# LEDs.net
KiCad netlist of a schematic drawn in Altium Designer
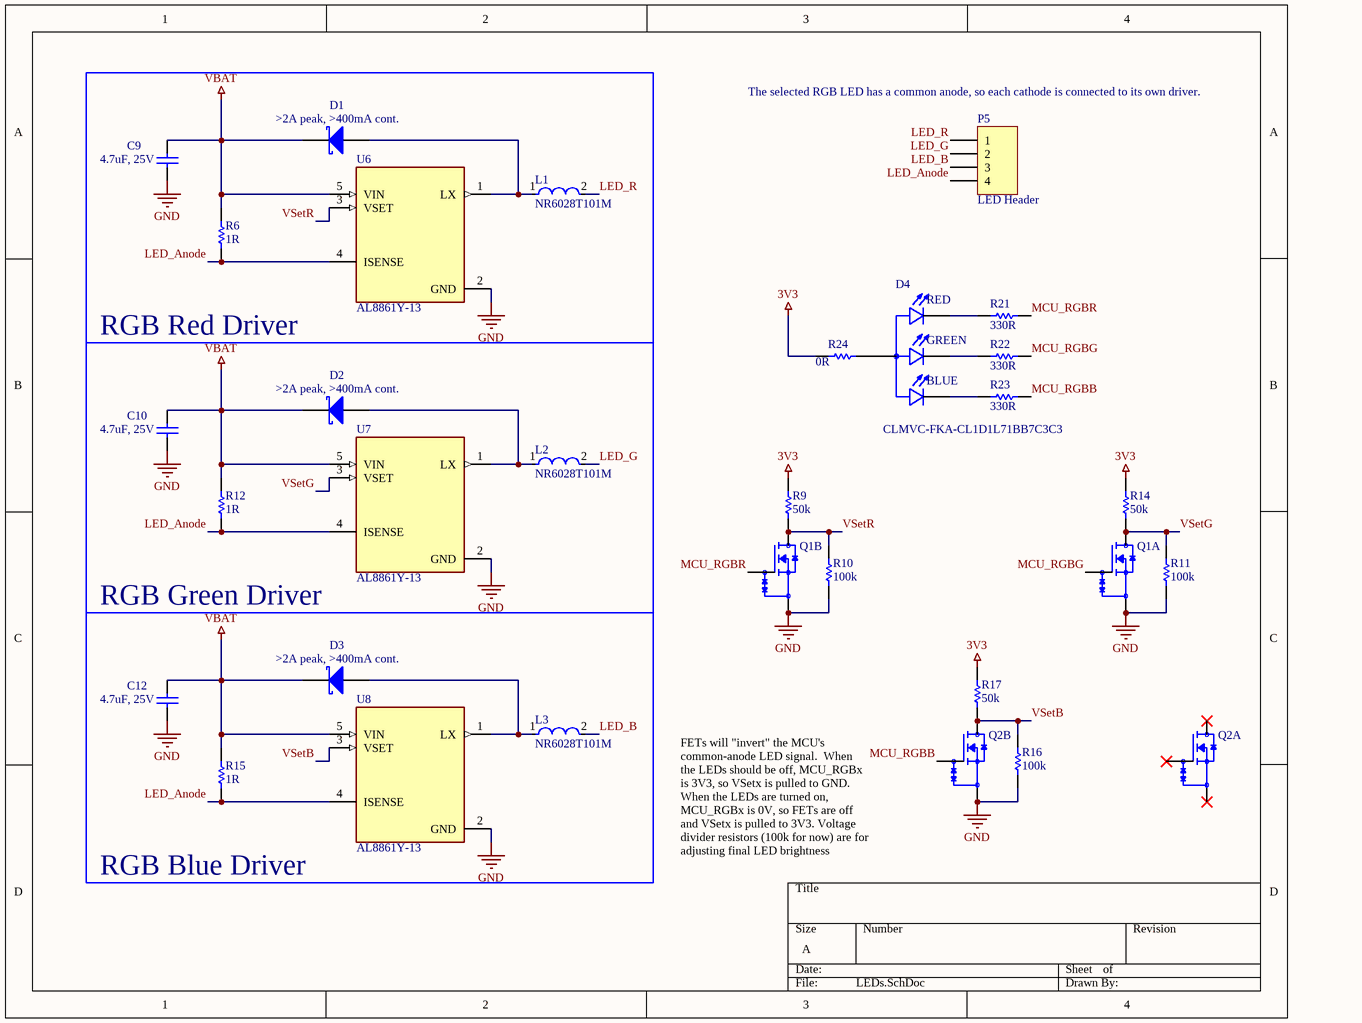
[diagram p0: LEDs.SchDoc]

(export (version "E")
  (design (tool "Eeschema 10.0.6"))
  (components
    (comp (ref "C9")
      (value "4.7uF, 25V")
      (footprint "ANTC1608X90N")
      (description "Capacitor")
      (libsource (lib "Simulation Generic Components") (part "Capacitor"))
    )
    (comp (ref "C10")
      (value "4.7uF, 25V")
      (footprint "ANTC1608X90N")
      (description "Capacitor")
      (libsource (lib "Simulation Generic Components") (part "Capacitor"))
    )
    (comp (ref "C12")
      (value "4.7uF, 25V")
      (footprint "ANTC1608X90N")
      (description "Capacitor")
      (libsource (lib "Simulation Generic Components") (part "Capacitor"))
    )
    (comp (ref "D1")
      (value ">2A peak, >400mA cont.")
      (footprint "DIO_SS26FL")
      (description "Shottky Diode")
      (libsource (lib "Simulation Generic Components") (part "Shottky Diode"))
    )
    (comp (ref "D2")
      (value ">2A peak, >400mA cont.")
      (footprint "DIO_SS26FL")
      (description "Shottky Diode")
      (libsource (lib "Simulation Generic Components") (part "Shottky Diode"))
    )
    (comp (ref "D3")
      (value ">2A peak, >400mA cont.")
      (footprint "DIO_SS26FL")
      (description "Shottky Diode")
      (libsource (lib "Simulation Generic Components") (part "Shottky Diode"))
    )
    (comp (ref "D4")
      (value "CLMVC-FKA-CL1D1L71BB7C3C3")
      (footprint "LED_CLMVC-FKA-CL1D1L71BB7C3C3")
      (fields (field (name "MF") "Cree Inc."))
      (libsource (lib "CLMVC-FKA-CL1D1L71BB7C3C3") (part "CLMVC-FKA-CL1D1L71BB7C3C3"))
    )
    (comp (ref "L1")
      (value "NR6028T101M")
      (footprint "FP-NR6028-MFG")
      (description "SMD Power Inductors 100uH ±20% 0.62A 0.78Ω")
      (fields (field (name "TOLERANCE") "20%"))
      (libsource (lib "Altium Content Vault") (part "725321dda6339637d4d059423bc1c3c"))
    )
    (comp (ref "L2")
      (value "NR6028T101M")
      (footprint "FP-NR6028-MFG")
      (description "SMD Power Inductors 100uH ±20% 0.62A 0.78Ω")
      (fields (field (name "TOLERANCE") "20%"))
      (libsource (lib "Altium Content Vault") (part "725321dda6339637d4d059423bc1c3c"))
    )
    (comp (ref "L3")
      (value "NR6028T101M")
      (footprint "FP-NR6028-MFG")
      (description "SMD Power Inductors 100uH ±20% 0.62A 0.78Ω")
      (fields (field (name "TOLERANCE") "20%"))
      (libsource (lib "Altium Content Vault") (part "725321dda6339637d4d059423bc1c3c"))
    )
    (comp (ref "P5")
      (value "LED Header")
      (footprint "TE_350761-4")
      (description "Header, 4-Pin")
      (fields (field (name "PUBLISHER") "Altium Limited"))
      (libsource (lib "Miscellaneous Connectors") (part "Header 4"))
    )
    (comp (ref "Q1")
      (value "TSM2N7002KDCU6_RFG")
      (footprint "SOT65P210X110-6N")
      (description "60V, 0.22A, Dual N-Channel Power MOSFET")
      (fields (field (name "MF") "Taiwan Semiconductor") (field (name "MP") "TSM2N7002KDCU6 RFG"))
      (libsource (lib "TSM2N7002KDCU6_RFG") (part "TSM2N7002KDCU6_RFG"))
    )
    (comp (ref "Q2")
      (value "TSM2N7002KDCU6_RFG")
      (footprint "SOT65P210X110-6N")
      (description "60V, 0.22A, Dual N-Channel Power MOSFET")
      (fields (field (name "MF") "Taiwan Semiconductor") (field (name "MP") "TSM2N7002KDCU6 RFG"))
      (libsource (lib "TSM2N7002KDCU6_RFG") (part "TSM2N7002KDCU6_RFG"))
    )
    (comp (ref "R6")
      (value "1R")
      (footprint "0603 Resistor")
      (description "Resistor")
      (libsource (lib "Simulation Generic Components") (part "Resistor"))
    )
    (comp (ref "R9")
      (value "50k")
      (footprint "0603 Resistor")
      (description "Resistor")
      (libsource (lib "Simulation Generic Components") (part "Resistor"))
    )
    (comp (ref "R10")
      (value "100k")
      (footprint "0603 Resistor")
      (description "Resistor")
      (libsource (lib "Simulation Generic Components") (part "Resistor"))
    )
    (comp (ref "R11")
      (value "100k")
      (footprint "0603 Resistor")
      (description "Resistor")
      (libsource (lib "Simulation Generic Components") (part "Resistor"))
    )
    (comp (ref "R12")
      (value "1R")
      (footprint "0603 Resistor")
      (description "Resistor")
      (libsource (lib "Simulation Generic Components") (part "Resistor"))
    )
    (comp (ref "R14")
      (value "50k")
      (footprint "0603 Resistor")
      (description "Resistor")
      (libsource (lib "Simulation Generic Components") (part "Resistor"))
    )
    (comp (ref "R15")
      (value "1R")
      (footprint "0603 Resistor")
      (description "Resistor")
      (libsource (lib "Simulation Generic Components") (part "Resistor"))
    )
    (comp (ref "R16")
      (value "100k")
      (footprint "0603 Resistor")
      (description "Resistor")
      (libsource (lib "Simulation Generic Components") (part "Resistor"))
    )
    (comp (ref "R17")
      (value "50k")
      (footprint "0603 Resistor")
      (description "Resistor")
      (libsource (lib "Simulation Generic Components") (part "Resistor"))
    )
    (comp (ref "R21")
      (value "330R")
      (footprint "0603 Resistor")
      (description "Resistor")
      (libsource (lib "Simulation Generic Components") (part "Resistor"))
    )
    (comp (ref "R22")
      (value "330R")
      (footprint "0603 Resistor")
      (description "Resistor")
      (libsource (lib "Simulation Generic Components") (part "Resistor"))
    )
    (comp (ref "R23")
      (value "330R")
      (footprint "0603 Resistor")
      (description "Resistor")
      (libsource (lib "Simulation Generic Components") (part "Resistor"))
    )
    (comp (ref "R24")
      (value "0R")
      (footprint "0603 Resistor")
      (description "Resistor")
      (libsource (lib "Simulation Generic Components") (part "Resistor"))
    )
    (comp (ref "U6")
      (value "AL8861Y-13")
      (footprint "CONV_AL8861Y-13")
      (description "LED Driver IC 1 Output DC DC Regulator Step-Down _Buck_ Analog, PWM Dimming 1.5A SOT-89-5")
      (fields (field (name "MF") "Diodes Inc."))
      (libsource (lib "AL8861Y-13") (part "AL8861Y-13"))
    )
    (comp (ref "U7")
      (value "AL8861Y-13")
      (footprint "CONV_AL8861Y-13")
      (description "LED Driver IC 1 Output DC DC Regulator Step-Down _Buck_ Analog, PWM Dimming 1.5A SOT-89-5")
      (fields (field (name "MF") "Diodes Inc."))
      (libsource (lib "AL8861Y-13") (part "AL8861Y-13"))
    )
    (comp (ref "U8")
      (value "AL8861Y-13")
      (footprint "CONV_AL8861Y-13")
      (description "LED Driver IC 1 Output DC DC Regulator Step-Down _Buck_ Analog, PWM Dimming 1.5A SOT-89-5")
      (fields (field (name "MF") "Diodes Inc."))
      (libsource (lib "AL8861Y-13") (part "AL8861Y-13"))
    )
  )
  (nets
    (net (code "1") (name "/LED_Anode") (class "Default")
      (node (ref "P5") (pin "4") (pinfunction "4_4") (pintype "passive"))
      (node (ref "R12") (pin "2") (pinfunction "2_2") (pintype "passive"))
      (node (ref "R15") (pin "2") (pinfunction "2_2") (pintype "passive"))
      (node (ref "R6") (pin "2") (pinfunction "2_2") (pintype "passive"))
      (node (ref "U6") (pin "4") (pinfunction "ISENSE_4") (pintype "passive"))
      (node (ref "U7") (pin "4") (pinfunction "ISENSE_4") (pintype "passive"))
      (node (ref "U8") (pin "4") (pinfunction "ISENSE_4") (pintype "passive"))
    )
    (net (code "2") (name "/LED_B") (class "Default")
      (node (ref "L3") (pin "2") (pinfunction "2_2") (pintype "passive"))
      (node (ref "P5") (pin "3") (pinfunction "3_3") (pintype "passive"))
    )
    (net (code "3") (name "/LED_G") (class "Default")
      (node (ref "L2") (pin "2") (pinfunction "2_2") (pintype "passive"))
      (node (ref "P5") (pin "2") (pinfunction "2_2") (pintype "passive"))
    )
    (net (code "4") (name "/LED_R") (class "Default")
      (node (ref "L1") (pin "2") (pinfunction "2_2") (pintype "passive"))
      (node (ref "P5") (pin "1") (pinfunction "1_1") (pintype "passive"))
    )
    (net (code "5") (name "/MCU_RGBB") (class "Default")
      (node (ref "Q2") (pin "5") (pinfunction "G2_5") (pintype "passive"))
      (node (ref "R23") (pin "2") (pinfunction "2_2") (pintype "passive"))
    )
    (net (code "6") (name "/MCU_RGBG") (class "Default")
      (node (ref "Q1") (pin "2") (pinfunction "G1_2") (pintype "passive"))
      (node (ref "R22") (pin "2") (pinfunction "2_2") (pintype "passive"))
    )
    (net (code "7") (name "/MCU_RGBR") (class "Default")
      (node (ref "Q1") (pin "5") (pinfunction "G2_5") (pintype "passive"))
      (node (ref "R21") (pin "2") (pinfunction "2_2") (pintype "passive"))
    )
    (net (code "8") (name "/VSetB") (class "Default")
      (node (ref "Q2") (pin "3") (pinfunction "D2_3") (pintype "passive"))
      (node (ref "R16") (pin "2") (pinfunction "2_2") (pintype "passive"))
      (node (ref "R17") (pin "1") (pinfunction "1_1") (pintype "passive"))
      (node (ref "U8") (pin "3") (pinfunction "VSET_3") (pintype "input"))
    )
    (net (code "9") (name "/VSetG") (class "Default")
      (node (ref "Q1") (pin "6") (pinfunction "D1_6") (pintype "passive"))
      (node (ref "R11") (pin "2") (pinfunction "2_2") (pintype "passive"))
      (node (ref "R14") (pin "1") (pinfunction "1_1") (pintype "passive"))
      (node (ref "U7") (pin "3") (pinfunction "VSET_3") (pintype "input"))
    )
    (net (code "10") (name "/VSetR") (class "Default")
      (node (ref "Q1") (pin "3") (pinfunction "D2_3") (pintype "passive"))
      (node (ref "R10") (pin "2") (pinfunction "2_2") (pintype "passive"))
      (node (ref "R9") (pin "1") (pinfunction "1_1") (pintype "passive"))
      (node (ref "U6") (pin "3") (pinfunction "VSET_3") (pintype "input"))
    )
    (net (code "11") (name "3V3") (class "Default")
      (node (ref "R14") (pin "2") (pinfunction "2_2") (pintype "passive"))
      (node (ref "R17") (pin "2") (pinfunction "2_2") (pintype "passive"))
      (node (ref "R24") (pin "1") (pinfunction "1_1") (pintype "passive"))
      (node (ref "R9") (pin "2") (pinfunction "2_2") (pintype "passive"))
    )
    (net (code "12") (name "GND") (class "Default")
      (node (ref "C10") (pin "1") (pinfunction "1_1") (pintype "passive"))
      (node (ref "C12") (pin "1") (pinfunction "1_1") (pintype "passive"))
      (node (ref "C9") (pin "1") (pinfunction "1_1") (pintype "passive"))
      (node (ref "Q1") (pin "1") (pinfunction "S1_1") (pintype "passive"))
      (node (ref "Q1") (pin "4") (pinfunction "S2_4") (pintype "passive"))
      (node (ref "Q2") (pin "4") (pinfunction "S2_4") (pintype "passive"))
      (node (ref "R10") (pin "1") (pinfunction "1_1") (pintype "passive"))
      (node (ref "R11") (pin "1") (pinfunction "1_1") (pintype "passive"))
      (node (ref "R16") (pin "1") (pinfunction "1_1") (pintype "passive"))
      (node (ref "U6") (pin "2") (pinfunction "GND_2") (pintype "power_in"))
      (node (ref "U7") (pin "2") (pinfunction "GND_2") (pintype "power_in"))
      (node (ref "U8") (pin "2") (pinfunction "GND_2") (pintype "power_in"))
    )
    (net (code "13") (name "Net-(D1-A)") (class "Default")
      (node (ref "D1") (pin "1") (pinfunction "A_1") (pintype "passive"))
      (node (ref "L1") (pin "1") (pinfunction "1_1") (pintype "passive"))
      (node (ref "U6") (pin "1") (pinfunction "LX_1") (pintype "output"))
    )
    (net (code "14") (name "Net-(D2-A)") (class "Default")
      (node (ref "D2") (pin "1") (pinfunction "A_1") (pintype "passive"))
      (node (ref "L2") (pin "1") (pinfunction "1_1") (pintype "passive"))
      (node (ref "U7") (pin "1") (pinfunction "LX_1") (pintype "output"))
    )
    (net (code "15") (name "Net-(D3-A)") (class "Default")
      (node (ref "D3") (pin "1") (pinfunction "A_1") (pintype "passive"))
      (node (ref "L3") (pin "1") (pinfunction "1_1") (pintype "passive"))
      (node (ref "U8") (pin "1") (pinfunction "LX_1") (pintype "output"))
    )
    (net (code "16") (name "Net-(D4-A)") (class "Default")
      (node (ref "D4") (pin "1") (pinfunction "A_1") (pintype "passive"))
      (node (ref "R24") (pin "2") (pinfunction "2_2") (pintype "passive"))
    )
    (net (code "17") (name "Net-(D4-B_C)") (class "Default")
      (node (ref "D4") (pin "2") (pinfunction "B_C_2") (pintype "passive"))
      (node (ref "R23") (pin "1") (pinfunction "1_1") (pintype "passive"))
    )
    (net (code "18") (name "Net-(D4-G_C)") (class "Default")
      (node (ref "D4") (pin "3") (pinfunction "G_C_3") (pintype "passive"))
      (node (ref "R22") (pin "1") (pinfunction "1_1") (pintype "passive"))
    )
    (net (code "19") (name "Net-(D4-R_C)") (class "Default")
      (node (ref "D4") (pin "4") (pinfunction "R_C_4") (pintype "passive"))
      (node (ref "R21") (pin "1") (pinfunction "1_1") (pintype "passive"))
    )
    (net (code "20") (name "VBAT") (class "Default")
      (node (ref "C10") (pin "2") (pinfunction "2_2") (pintype "passive"))
      (node (ref "C12") (pin "2") (pinfunction "2_2") (pintype "passive"))
      (node (ref "C9") (pin "2") (pinfunction "2_2") (pintype "passive"))
      (node (ref "D1") (pin "2") (pinfunction "K_2") (pintype "passive"))
      (node (ref "D2") (pin "2") (pinfunction "K_2") (pintype "passive"))
      (node (ref "D3") (pin "2") (pinfunction "K_2") (pintype "passive"))
      (node (ref "R12") (pin "1") (pinfunction "1_1") (pintype "passive"))
      (node (ref "R15") (pin "1") (pinfunction "1_1") (pintype "passive"))
      (node (ref "R6") (pin "1") (pinfunction "1_1") (pintype "passive"))
      (node (ref "U6") (pin "5") (pinfunction "VIN_5") (pintype "input"))
      (node (ref "U7") (pin "5") (pinfunction "VIN_5") (pintype "input"))
      (node (ref "U8") (pin "5") (pinfunction "VIN_5") (pintype "input"))
    )
    (net (code "21") (name "unconnected-(Q2A-D1-Pad6)") (class "Default")
      (node (ref "Q2") (pin "6") (pinfunction "D1_6") (pintype "passive+no_connect"))
    )
    (net (code "22") (name "unconnected-(Q2A-G1-Pad2)") (class "Default")
      (node (ref "Q2") (pin "2") (pinfunction "G1_2") (pintype "passive+no_connect"))
    )
    (net (code "23") (name "unconnected-(Q2A-S1-Pad1)") (class "Default")
      (node (ref "Q2") (pin "1") (pinfunction "S1_1") (pintype "passive+no_connect"))
    )
  )
)
